# Wheel_Encoder_Adapter_Schmitt_74xx.net
KiCad netlist of a schematic drawn in EAGLE
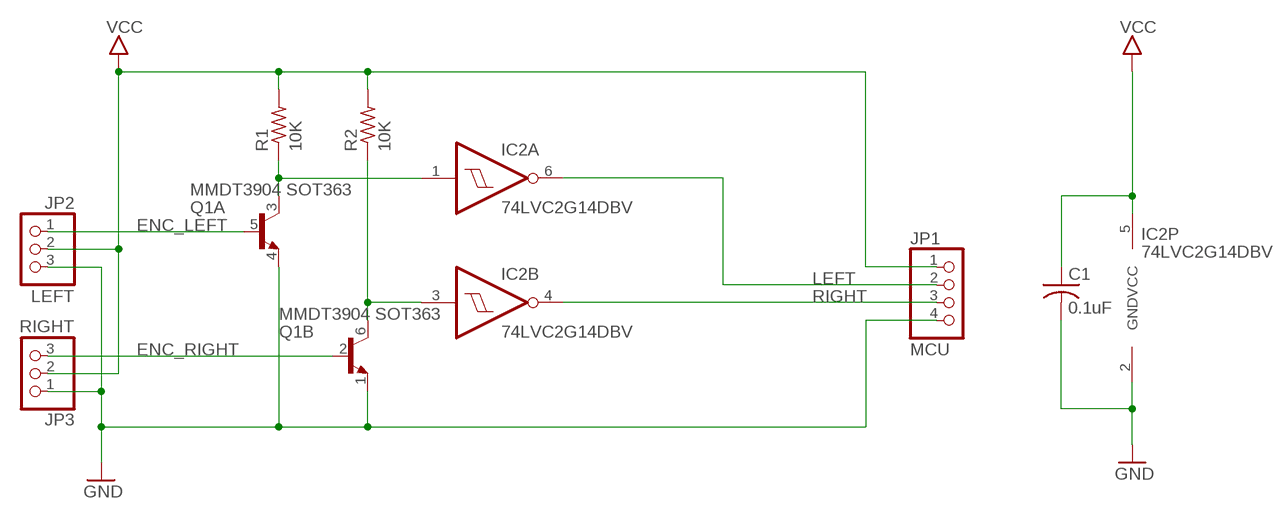
[diagram p0: schematic, sheet 1]

(export (version "E")
  (design (tool "Eeschema 10.0.6"))
  (components
    (comp (ref "C1")
      (value "0.1uF")
      (footprint "eagle-import:C0603")
      (libsource (lib "eagle-import") (part "C-USC0603"))
    )
    (comp (ref "IC2")
      (value "74LVC2G14DBV")
      (footprint "eagle-import:SOT23-6")
      (libsource (lib "eagle-import") (part "74LVC2G14DBV"))
    )
    (comp (ref "JP1")
      (value "MCU")
      (footprint "eagle-import:1X04-S")
      (libsource (lib "eagle-import") (part "PINHD-1X04_2.54-S"))
    )
    (comp (ref "JP2")
      (value "LEFT")
      (footprint "eagle-import:1X03-S")
      (libsource (lib "eagle-import") (part "PINHD-1X03_2.54-S"))
    )
    (comp (ref "JP3")
      (value "RIGHT")
      (footprint "eagle-import:1X03-S")
      (libsource (lib "eagle-import") (part "PINHD-1X03_2.54-S"))
    )
    (comp (ref "Q1")
      (value "MMDT3904 SOT363")
      (footprint "eagle-import:SOT363")
      (libsource (lib "eagle-import") (part "MBT3904DW1"))
    )
    (comp (ref "R1")
      (value "10K")
      (footprint "eagle-import:R0603")
      (libsource (lib "eagle-import") (part "R-US_R0603"))
    )
    (comp (ref "R2")
      (value "10K")
      (footprint "eagle-import:R0603")
      (libsource (lib "eagle-import") (part "R-US_R0603"))
    )
  )
  (nets
    (net (code "1") (name "/ENC_LEFT") (class "Default")
      (node (ref "JP2") (pin "1") (pinfunction "1_1") (pintype "passive"))
      (node (ref "Q1") (pin "5") (pinfunction "B_5") (pintype "passive"))
    )
    (net (code "2") (name "/ENC_RIGHT") (class "Default")
      (node (ref "JP3") (pin "3") (pinfunction "3_3") (pintype "passive"))
      (node (ref "Q1") (pin "2") (pinfunction "B_2") (pintype "passive"))
    )
    (net (code "3") (name "/LEFT") (class "Default")
      (node (ref "IC2") (pin "6") (pinfunction "O_6") (pintype "output"))
      (node (ref "JP1") (pin "2") (pinfunction "2_2") (pintype "passive"))
    )
    (net (code "4") (name "/RIGHT") (class "Default")
      (node (ref "IC2") (pin "4") (pinfunction "O_4") (pintype "output"))
      (node (ref "JP1") (pin "3") (pinfunction "3_3") (pintype "passive"))
    )
    (net (code "5") (name "GND") (class "Default")
      (node (ref "C1") (pin "2") (pinfunction "2_2") (pintype "passive"))
      (node (ref "IC2") (pin "2") (pinfunction "GND_2") (pintype "power_in"))
      (node (ref "JP1") (pin "4") (pinfunction "4_4") (pintype "passive"))
      (node (ref "JP2") (pin "3") (pinfunction "3_3") (pintype "passive"))
      (node (ref "JP3") (pin "1") (pinfunction "1_1") (pintype "passive"))
      (node (ref "Q1") (pin "1") (pinfunction "E_1") (pintype "passive"))
      (node (ref "Q1") (pin "4") (pinfunction "E_4") (pintype "passive"))
    )
    (net (code "6") (name "Net-(IC2A-I)") (class "Default")
      (node (ref "IC2") (pin "1") (pinfunction "I_1") (pintype "input"))
      (node (ref "Q1") (pin "3") (pinfunction "C_3") (pintype "passive"))
      (node (ref "R1") (pin "1") (pinfunction "1_1") (pintype "passive"))
    )
    (net (code "7") (name "Net-(IC2B-I)") (class "Default")
      (node (ref "IC2") (pin "3") (pinfunction "I_3") (pintype "input"))
      (node (ref "Q1") (pin "6") (pinfunction "C_6") (pintype "passive"))
      (node (ref "R2") (pin "1") (pinfunction "1_1") (pintype "passive"))
    )
    (net (code "8") (name "VCC") (class "Default")
      (node (ref "C1") (pin "1") (pinfunction "1_1") (pintype "passive"))
      (node (ref "IC2") (pin "5") (pinfunction "VCC_5") (pintype "power_in"))
      (node (ref "JP1") (pin "1") (pinfunction "1_1") (pintype "passive"))
      (node (ref "JP2") (pin "2") (pinfunction "2_2") (pintype "passive"))
      (node (ref "JP3") (pin "2") (pinfunction "2_2") (pintype "passive"))
      (node (ref "R1") (pin "2") (pinfunction "2_2") (pintype "passive"))
      (node (ref "R2") (pin "2") (pinfunction "2_2") (pintype "passive"))
    )
  )
)
